# Multivibrator.net
KiCad netlist of a schematic drawn in Altium Designer
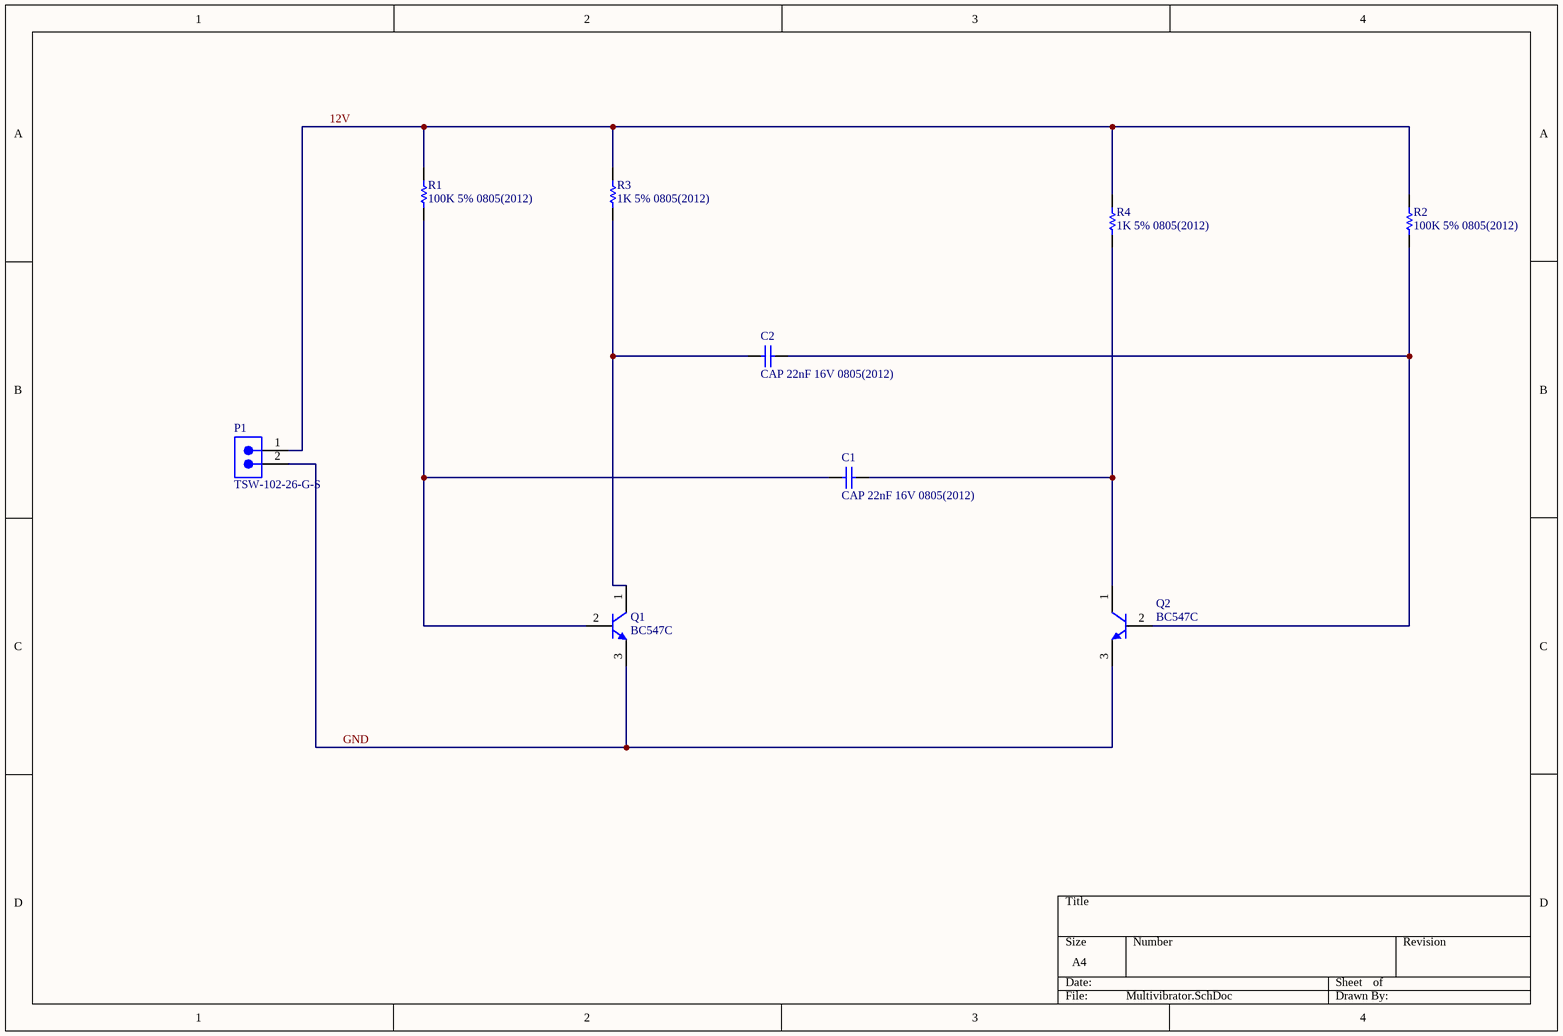
[diagram p0: Multivibrator.SchDoc]

(export (version "E")
  (design (tool "Eeschema 10.0.6"))
  (components
    (comp (ref "C1")
      (value "CAP 22nF 16V 0805(2012)")
      (footprint "CAPC0805(2012)145_N")
      (description "CAP 22nF 16V ±10% 0805 (2012 Metric) Thickness 1.45mm SMD")
      (fields (field (name "TOLERANCE") "Â±10%"))
      (libsource (lib "Altium Content Vault") (part "CAP"))
    )
    (comp (ref "C2")
      (value "CAP 22nF 16V 0805(2012)")
      (footprint "CAPC0805(2012)145_N")
      (description "CAP 22nF 16V ±10% 0805 (2012 Metric) Thickness 1.45mm SMD")
      (fields (field (name "TOLERANCE") "Â±10%"))
      (libsource (lib "Altium Content Vault") (part "CAP"))
    )
    (comp (ref "P1")
      (value "TSW-102-26-G-S")
      (footprint "SMTC-TSW-102-26-XX-S")
      (fields (field (name "MANUFACTURER") "Samtec"))
      (libsource (lib "Altium Content Vault") (part "SMTC-TSW-102-X-X-S-X"))
    )
    (comp (ref "Q1")
      (value "BC547C")
      (footprint "ONSC-TO-92-3-29-11")
      (description "Amplifier Transistor, NPN Silicon, 3-Pin TO-92, Bulk Box")
      (fields (field (name "MANUFACTURER") "On Semiconductor"))
      (libsource (lib "Altium Content Vault") (part "ONSC-NPN-C1B2E3-3"))
    )
    (comp (ref "Q2")
      (value "BC547C")
      (footprint "ONSC-TO-92-3-29-11")
      (description "Amplifier Transistor, NPN Silicon, 3-Pin TO-92, Bulk Box")
      (fields (field (name "MANUFACTURER") "On Semiconductor"))
      (libsource (lib "Altium Content Vault") (part "ONSC-NPN-C1B2E3-3"))
    )
    (comp (ref "R1")
      (value "100K 5% 0805(2012)")
      (footprint "RESC0805(2012)_L")
      (description "100K 0.125W 5% 0805 (2012 Metric)  SMD")
      (fields (field (name "TOLERANCE") "5 %") (field (name "POWER") "0.125 W"))
      (libsource (lib "Altium Content Vault") (part "RES"))
    )
    (comp (ref "R2")
      (value "100K 5% 0805(2012)")
      (footprint "RESC0805(2012)_L")
      (description "100K 0.125W 5% 0805 (2012 Metric)  SMD")
      (fields (field (name "TOLERANCE") "5 %") (field (name "POWER") "0.125 W"))
      (libsource (lib "Altium Content Vault") (part "RES"))
    )
    (comp (ref "R3")
      (value "1K 5% 0805(2012)")
      (footprint "RESC0805(2012)_N")
      (description "1K 0.125W 5% 0805 (2012 Metric)  SMD")
      (fields (field (name "POWER") "0.125 W") (field (name "TOLERANCE") "5 %"))
      (libsource (lib "Altium Content Vault") (part "RES"))
    )
    (comp (ref "R4")
      (value "1K 5% 0805(2012)")
      (footprint "RESC0805(2012)_N")
      (description "1K 0.125W 5% 0805 (2012 Metric)  SMD")
      (fields (field (name "POWER") "0.125 W") (field (name "TOLERANCE") "5 %"))
      (libsource (lib "Altium Content Vault") (part "RES"))
    )
  )
  (nets
    (net (code "1") (name "/12V") (class "Default")
      (node (ref "P1") (pin "1") (pinfunction "1_1") (pintype "passive"))
      (node (ref "R1") (pin "1") (pinfunction "1_1") (pintype "passive"))
      (node (ref "R2") (pin "1") (pinfunction "1_1") (pintype "passive"))
      (node (ref "R3") (pin "2") (pinfunction "2_2") (pintype "passive"))
      (node (ref "R4") (pin "2") (pinfunction "2_2") (pintype "passive"))
    )
    (net (code "2") (name "/GND") (class "Default")
      (node (ref "P1") (pin "2") (pinfunction "2_2") (pintype "passive"))
      (node (ref "Q1") (pin "3") (pinfunction "E_3") (pintype "passive"))
      (node (ref "Q2") (pin "3") (pinfunction "E_3") (pintype "passive"))
    )
    (net (code "3") (name "Net-(Q1-B)") (class "Default")
      (node (ref "C1") (pin "1") (pinfunction "1_1") (pintype "passive"))
      (node (ref "Q1") (pin "2") (pinfunction "B_2") (pintype "passive"))
      (node (ref "R1") (pin "2") (pinfunction "2_2") (pintype "passive"))
    )
    (net (code "4") (name "Net-(Q1-C)") (class "Default")
      (node (ref "C2") (pin "1") (pinfunction "1_1") (pintype "passive"))
      (node (ref "Q1") (pin "1") (pinfunction "C_1") (pintype "passive"))
      (node (ref "R3") (pin "1") (pinfunction "1_1") (pintype "passive"))
    )
    (net (code "5") (name "Net-(Q2-B)") (class "Default")
      (node (ref "C2") (pin "2") (pinfunction "2_2") (pintype "passive"))
      (node (ref "Q2") (pin "2") (pinfunction "B_2") (pintype "passive"))
      (node (ref "R2") (pin "2") (pinfunction "2_2") (pintype "passive"))
    )
    (net (code "6") (name "Net-(Q2-C)") (class "Default")
      (node (ref "C1") (pin "2") (pinfunction "2_2") (pintype "passive"))
      (node (ref "Q2") (pin "1") (pinfunction "C_1") (pintype "passive"))
      (node (ref "R4") (pin "1") (pinfunction "1_1") (pintype "passive"))
    )
  )
)
